# DiPho_devboard.net
KiCad netlist of a schematic drawn in Altium Designer
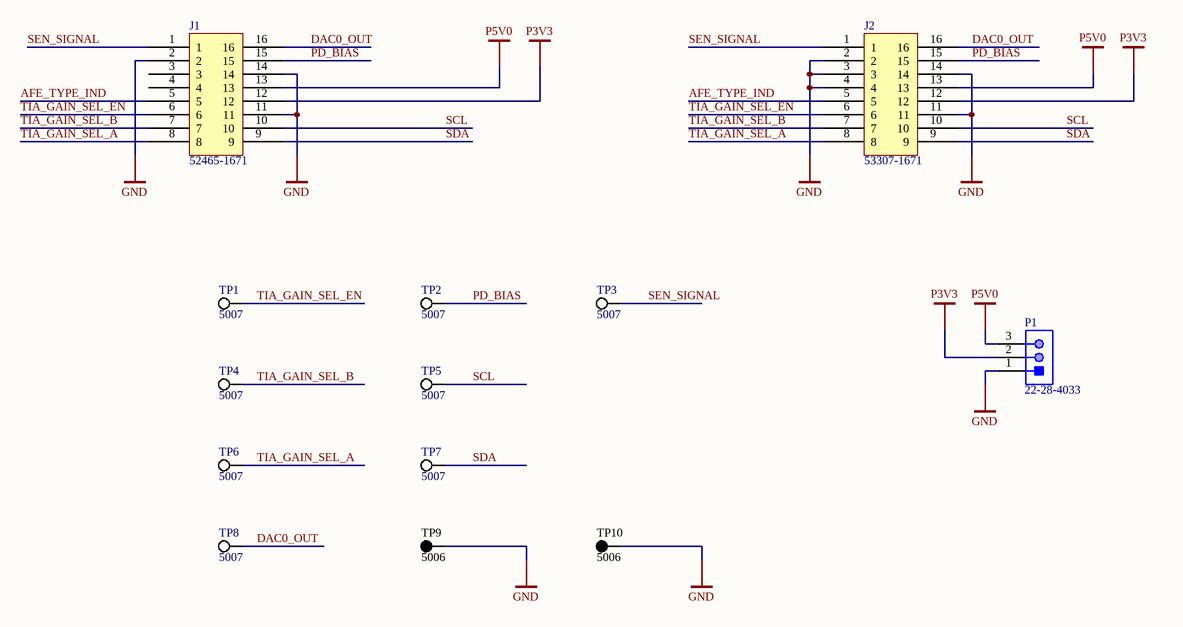
[diagram p0: DiPho_devboard.SchDoc]

(export (version "E")
  (design (tool "Eeschema 10.0.6"))
  (components
    (comp (ref "J1")
      (value "52465-1671")
      (footprint "524651671")
      (description "A Connector for Board - Board Connections with A 0.80 mm Pitch. (Molex)")
      (fields (field (name "MANUFACTURER") "Molex"))
      (libsource (lib "DiPho_lib") (part "52465-1671"))
    )
    (comp (ref "J2")
      (value "53307-1671")
      (footprint "533071671")
      (fields (field (name "MANUFACTURER") "Molex"))
      (libsource (lib "DiPho_lib") (part "53307-1671"))
    )
    (comp (ref "P1")
      (value "22-28-4033")
      (footprint "MOLX-22-28-4033_V")
      (description "Male Header, Pitch 2.54 mm, 1 x 3 Position, Height 8.38 mm, Tail Length 3.18 mm, RoHS, Bulk")
      (fields (field (name "MANUFACTURER") "Molex"))
      (libsource (lib "Altium Content Vault") (part "CN-1P-M-R3"))
    )
    (comp (ref "TP1")
      (value "5007")
      (footprint "KSTN-5012_V")
      (description "Test Point, White, Through Hole, RoHS, Bulk")
      (fields (field (name "MANUFACTURER") "Keystone"))
      (libsource (lib "Altium Content Vault") (part "TESTPOINT_WHITE"))
    )
    (comp (ref "TP2")
      (value "5007")
      (footprint "KSTN-5012_V")
      (description "Test Point, White, Through Hole, RoHS, Bulk")
      (fields (field (name "MANUFACTURER") "Keystone"))
      (libsource (lib "Altium Content Vault") (part "TESTPOINT_WHITE"))
    )
    (comp (ref "TP3")
      (value "5007")
      (footprint "KSTN-5012_V")
      (description "Test Point, White, Through Hole, RoHS, Bulk")
      (fields (field (name "MANUFACTURER") "Keystone"))
      (libsource (lib "Altium Content Vault") (part "TESTPOINT_WHITE"))
    )
    (comp (ref "TP4")
      (value "5007")
      (footprint "KSTN-5012_V")
      (description "Test Point, White, Through Hole, RoHS, Bulk")
      (fields (field (name "MANUFACTURER") "Keystone"))
      (libsource (lib "Altium Content Vault") (part "TESTPOINT_WHITE"))
    )
    (comp (ref "TP5")
      (value "5007")
      (footprint "KSTN-5012_V")
      (description "Test Point, White, Through Hole, RoHS, Bulk")
      (fields (field (name "MANUFACTURER") "Keystone"))
      (libsource (lib "Altium Content Vault") (part "TESTPOINT_WHITE"))
    )
    (comp (ref "TP6")
      (value "5007")
      (footprint "KSTN-5012_V")
      (description "Test Point, White, Through Hole, RoHS, Bulk")
      (fields (field (name "MANUFACTURER") "Keystone"))
      (libsource (lib "Altium Content Vault") (part "TESTPOINT_WHITE"))
    )
    (comp (ref "TP7")
      (value "5007")
      (footprint "KSTN-5012_V")
      (description "Test Point, White, Through Hole, RoHS, Bulk")
      (fields (field (name "MANUFACTURER") "Keystone"))
      (libsource (lib "Altium Content Vault") (part "TESTPOINT_WHITE"))
    )
    (comp (ref "TP8")
      (value "5007")
      (footprint "KSTN-5012_V")
      (description "Test Point, White, Through Hole, RoHS, Bulk")
      (fields (field (name "MANUFACTURER") "Keystone"))
      (libsource (lib "Altium Content Vault") (part "TESTPOINT_WHITE"))
    )
    (comp (ref "TP9")
      (value "5006")
      (footprint "KSTN-5011_V")
      (description "Test Point, Black, Through Hole, RoHS, Bulk")
      (fields (field (name "MANUFACTURER") "Keystone"))
      (libsource (lib "Altium Content Vault") (part "TESTPOINT_BLACK"))
    )
    (comp (ref "TP10")
      (value "5006")
      (footprint "KSTN-5011_V")
      (description "Test Point, Black, Through Hole, RoHS, Bulk")
      (fields (field (name "MANUFACTURER") "Keystone"))
      (libsource (lib "Altium Content Vault") (part "TESTPOINT_BLACK"))
    )
  )
  (nets
    (net (code "1") (name "/AFE_TYPE_IND") (class "Default")
      (node (ref "J1") (pin "5") (pinfunction "5_5") (pintype "passive"))
      (node (ref "J2") (pin "5") (pinfunction "5_5") (pintype "passive"))
    )
    (net (code "2") (name "/DAC0_OUT") (class "Default")
      (node (ref "J1") (pin "16") (pinfunction "16_16") (pintype "passive"))
      (node (ref "J2") (pin "16") (pinfunction "16_16") (pintype "passive"))
      (node (ref "TP8") (pin "1") (pinfunction "1_1") (pintype "passive"))
    )
    (net (code "3") (name "/PD_BIAS") (class "Default")
      (node (ref "J1") (pin "15") (pinfunction "15_15") (pintype "passive"))
      (node (ref "J2") (pin "15") (pinfunction "15_15") (pintype "passive"))
      (node (ref "TP2") (pin "1") (pinfunction "1_1") (pintype "passive"))
    )
    (net (code "4") (name "/SCL") (class "Default")
      (node (ref "J1") (pin "10") (pinfunction "10_10") (pintype "passive"))
      (node (ref "J2") (pin "10") (pinfunction "10_10") (pintype "passive"))
      (node (ref "TP5") (pin "1") (pinfunction "1_1") (pintype "passive"))
    )
    (net (code "5") (name "/SDA") (class "Default")
      (node (ref "J1") (pin "9") (pinfunction "9_9") (pintype "passive"))
      (node (ref "J2") (pin "9") (pinfunction "9_9") (pintype "passive"))
      (node (ref "TP7") (pin "1") (pinfunction "1_1") (pintype "passive"))
    )
    (net (code "6") (name "/SEN_SIGNAL") (class "Default")
      (node (ref "J1") (pin "1") (pinfunction "1_1") (pintype "passive"))
      (node (ref "J2") (pin "1") (pinfunction "1_1") (pintype "passive"))
      (node (ref "TP3") (pin "1") (pinfunction "1_1") (pintype "passive"))
    )
    (net (code "7") (name "/TIA_GAIN_SEL_A") (class "Default")
      (node (ref "J1") (pin "8") (pinfunction "8_8") (pintype "passive"))
      (node (ref "J2") (pin "8") (pinfunction "8_8") (pintype "passive"))
      (node (ref "TP6") (pin "1") (pinfunction "1_1") (pintype "passive"))
    )
    (net (code "8") (name "/TIA_GAIN_SEL_B") (class "Default")
      (node (ref "J1") (pin "7") (pinfunction "7_7") (pintype "passive"))
      (node (ref "J2") (pin "7") (pinfunction "7_7") (pintype "passive"))
      (node (ref "TP4") (pin "1") (pinfunction "1_1") (pintype "passive"))
    )
    (net (code "9") (name "/TIA_GAIN_SEL_EN") (class "Default")
      (node (ref "J1") (pin "6") (pinfunction "6_6") (pintype "passive"))
      (node (ref "J2") (pin "6") (pinfunction "6_6") (pintype "passive"))
      (node (ref "TP1") (pin "1") (pinfunction "1_1") (pintype "passive"))
    )
    (net (code "10") (name "GND") (class "Default")
      (node (ref "J1") (pin "11") (pinfunction "11_11") (pintype "passive"))
      (node (ref "J1") (pin "14") (pinfunction "14_14") (pintype "passive"))
      (node (ref "J1") (pin "2") (pinfunction "2_2") (pintype "passive"))
      (node (ref "J2") (pin "11") (pinfunction "11_11") (pintype "passive"))
      (node (ref "J2") (pin "14") (pinfunction "14_14") (pintype "passive"))
      (node (ref "J2") (pin "2") (pinfunction "2_2") (pintype "passive"))
      (node (ref "J2") (pin "3") (pinfunction "3_3") (pintype "passive"))
      (node (ref "J2") (pin "4") (pinfunction "4_4") (pintype "passive"))
      (node (ref "P1") (pin "1") (pinfunction "1_1") (pintype "passive"))
      (node (ref "TP10") (pin "1") (pinfunction "1_1") (pintype "passive"))
      (node (ref "TP9") (pin "1") (pinfunction "1_1") (pintype "passive"))
    )
    (net (code "11") (name "P3V3") (class "Default")
      (node (ref "J1") (pin "12") (pinfunction "12_12") (pintype "passive"))
      (node (ref "J2") (pin "12") (pinfunction "12_12") (pintype "passive"))
      (node (ref "P1") (pin "2") (pinfunction "2_2") (pintype "passive"))
    )
    (net (code "12") (name "P5V0") (class "Default")
      (node (ref "J1") (pin "13") (pinfunction "13_13") (pintype "passive"))
      (node (ref "J2") (pin "13") (pinfunction "13_13") (pintype "passive"))
      (node (ref "P1") (pin "3") (pinfunction "3_3") (pintype "passive"))
    )
    (net (code "13") (name "unconnected-(J1-Pad3)") (class "Default")
      (node (ref "J1") (pin "3") (pinfunction "3_3") (pintype "passive"))
    )
    (net (code "14") (name "unconnected-(J1-Pad4)") (class "Default")
      (node (ref "J1") (pin "4") (pinfunction "4_4") (pintype "passive"))
    )
  )
)
